# Fdbk_1.net
KiCad netlist of a schematic drawn in Altium Designer
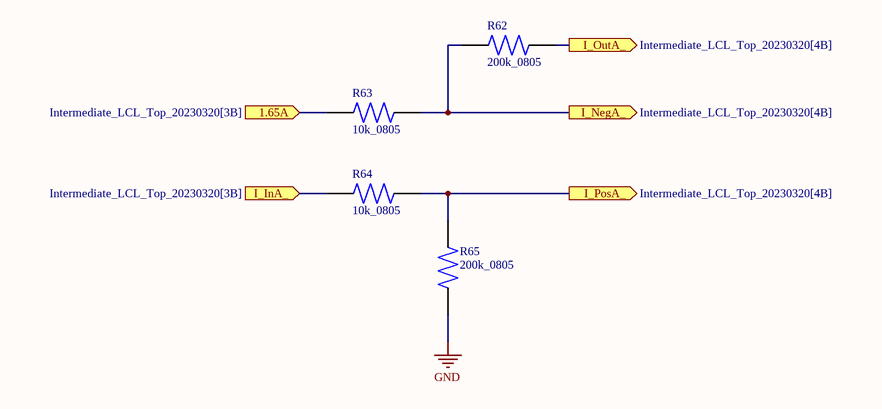
[diagram p0: Fdbk_1.SchDoc]

(export (version "E")
  (design (tool "Eeschema 10.0.6"))
  (components
    (comp (ref "R62")
      (value "200k_0805")
      (footprint "FYP_Components:0805 Resistor")
      (description "SMD Chip Resistor, 200 kohm, ± 1%, 125 mW, 0805 [2012 Metric], Thick Film, General Purpose")
      (fields (field (name "MF") "Bourns") (field (name "MP") "CRE2512-FZ-R007E-3"))
      (libsource (lib "FYP_Components") (part "CRCW0805200KFKEA"))
    )
    (comp (ref "R63")
      (value "10k_0805")
      (footprint "FYP_Components:0805 Resistor")
      (description "SMD Chip Resistor, 10 kohm, ± 1%, 125 mW, 0805 [2012 Metric], Thick Film, General Purpose")
      (fields (field (name "MF") "Bourns") (field (name "MP") "CRE2512-FZ-R007E-3"))
      (libsource (lib "FYP_Components") (part "CRCW080510K0FKEA"))
    )
    (comp (ref "R64")
      (value "10k_0805")
      (footprint "FYP_Components:0805 Resistor")
      (description "SMD Chip Resistor, 10 kohm, ± 1%, 125 mW, 0805 [2012 Metric], Thick Film, General Purpose")
      (fields (field (name "MF") "Bourns") (field (name "MP") "CRE2512-FZ-R007E-3"))
      (libsource (lib "FYP_Components") (part "CRCW080510K0FKEA"))
    )
    (comp (ref "R65")
      (value "200k_0805")
      (footprint "FYP_Components:0805 Resistor")
      (description "SMD Chip Resistor, 200 kohm, ± 1%, 125 mW, 0805 [2012 Metric], Thick Film, General Purpose")
      (fields (field (name "MF") "Bourns") (field (name "MP") "CRE2512-FZ-R007E-3"))
      (libsource (lib "FYP_Components") (part "CRCW0805200KFKEA"))
    )
  )
  (nets
    (net (code "1") (name "/1.65A") (class "Default")
      (node (ref "R63") (pin "1") (pinfunction "1_1") (pintype "passive"))
    )
    (net (code "2") (name "/I_InA_") (class "Default")
      (node (ref "R64") (pin "1") (pinfunction "1_1") (pintype "passive"))
    )
    (net (code "3") (name "/I_NegA_") (class "Default")
      (node (ref "R62") (pin "1") (pinfunction "1_1") (pintype "passive"))
      (node (ref "R63") (pin "2") (pinfunction "2_2") (pintype "passive"))
    )
    (net (code "4") (name "/I_OutA_") (class "Default")
      (node (ref "R62") (pin "2") (pinfunction "2_2") (pintype "passive"))
    )
    (net (code "5") (name "/I_PosA_") (class "Default")
      (node (ref "R64") (pin "2") (pinfunction "2_2") (pintype "passive"))
      (node (ref "R65") (pin "2") (pinfunction "2_2") (pintype "passive"))
    )
    (net (code "6") (name "GND") (class "Default")
      (node (ref "R65") (pin "1") (pinfunction "1_1") (pintype "passive"))
    )
  )
)
